# Schematic.net
KiCad netlist of a schematic drawn in Altium Designer
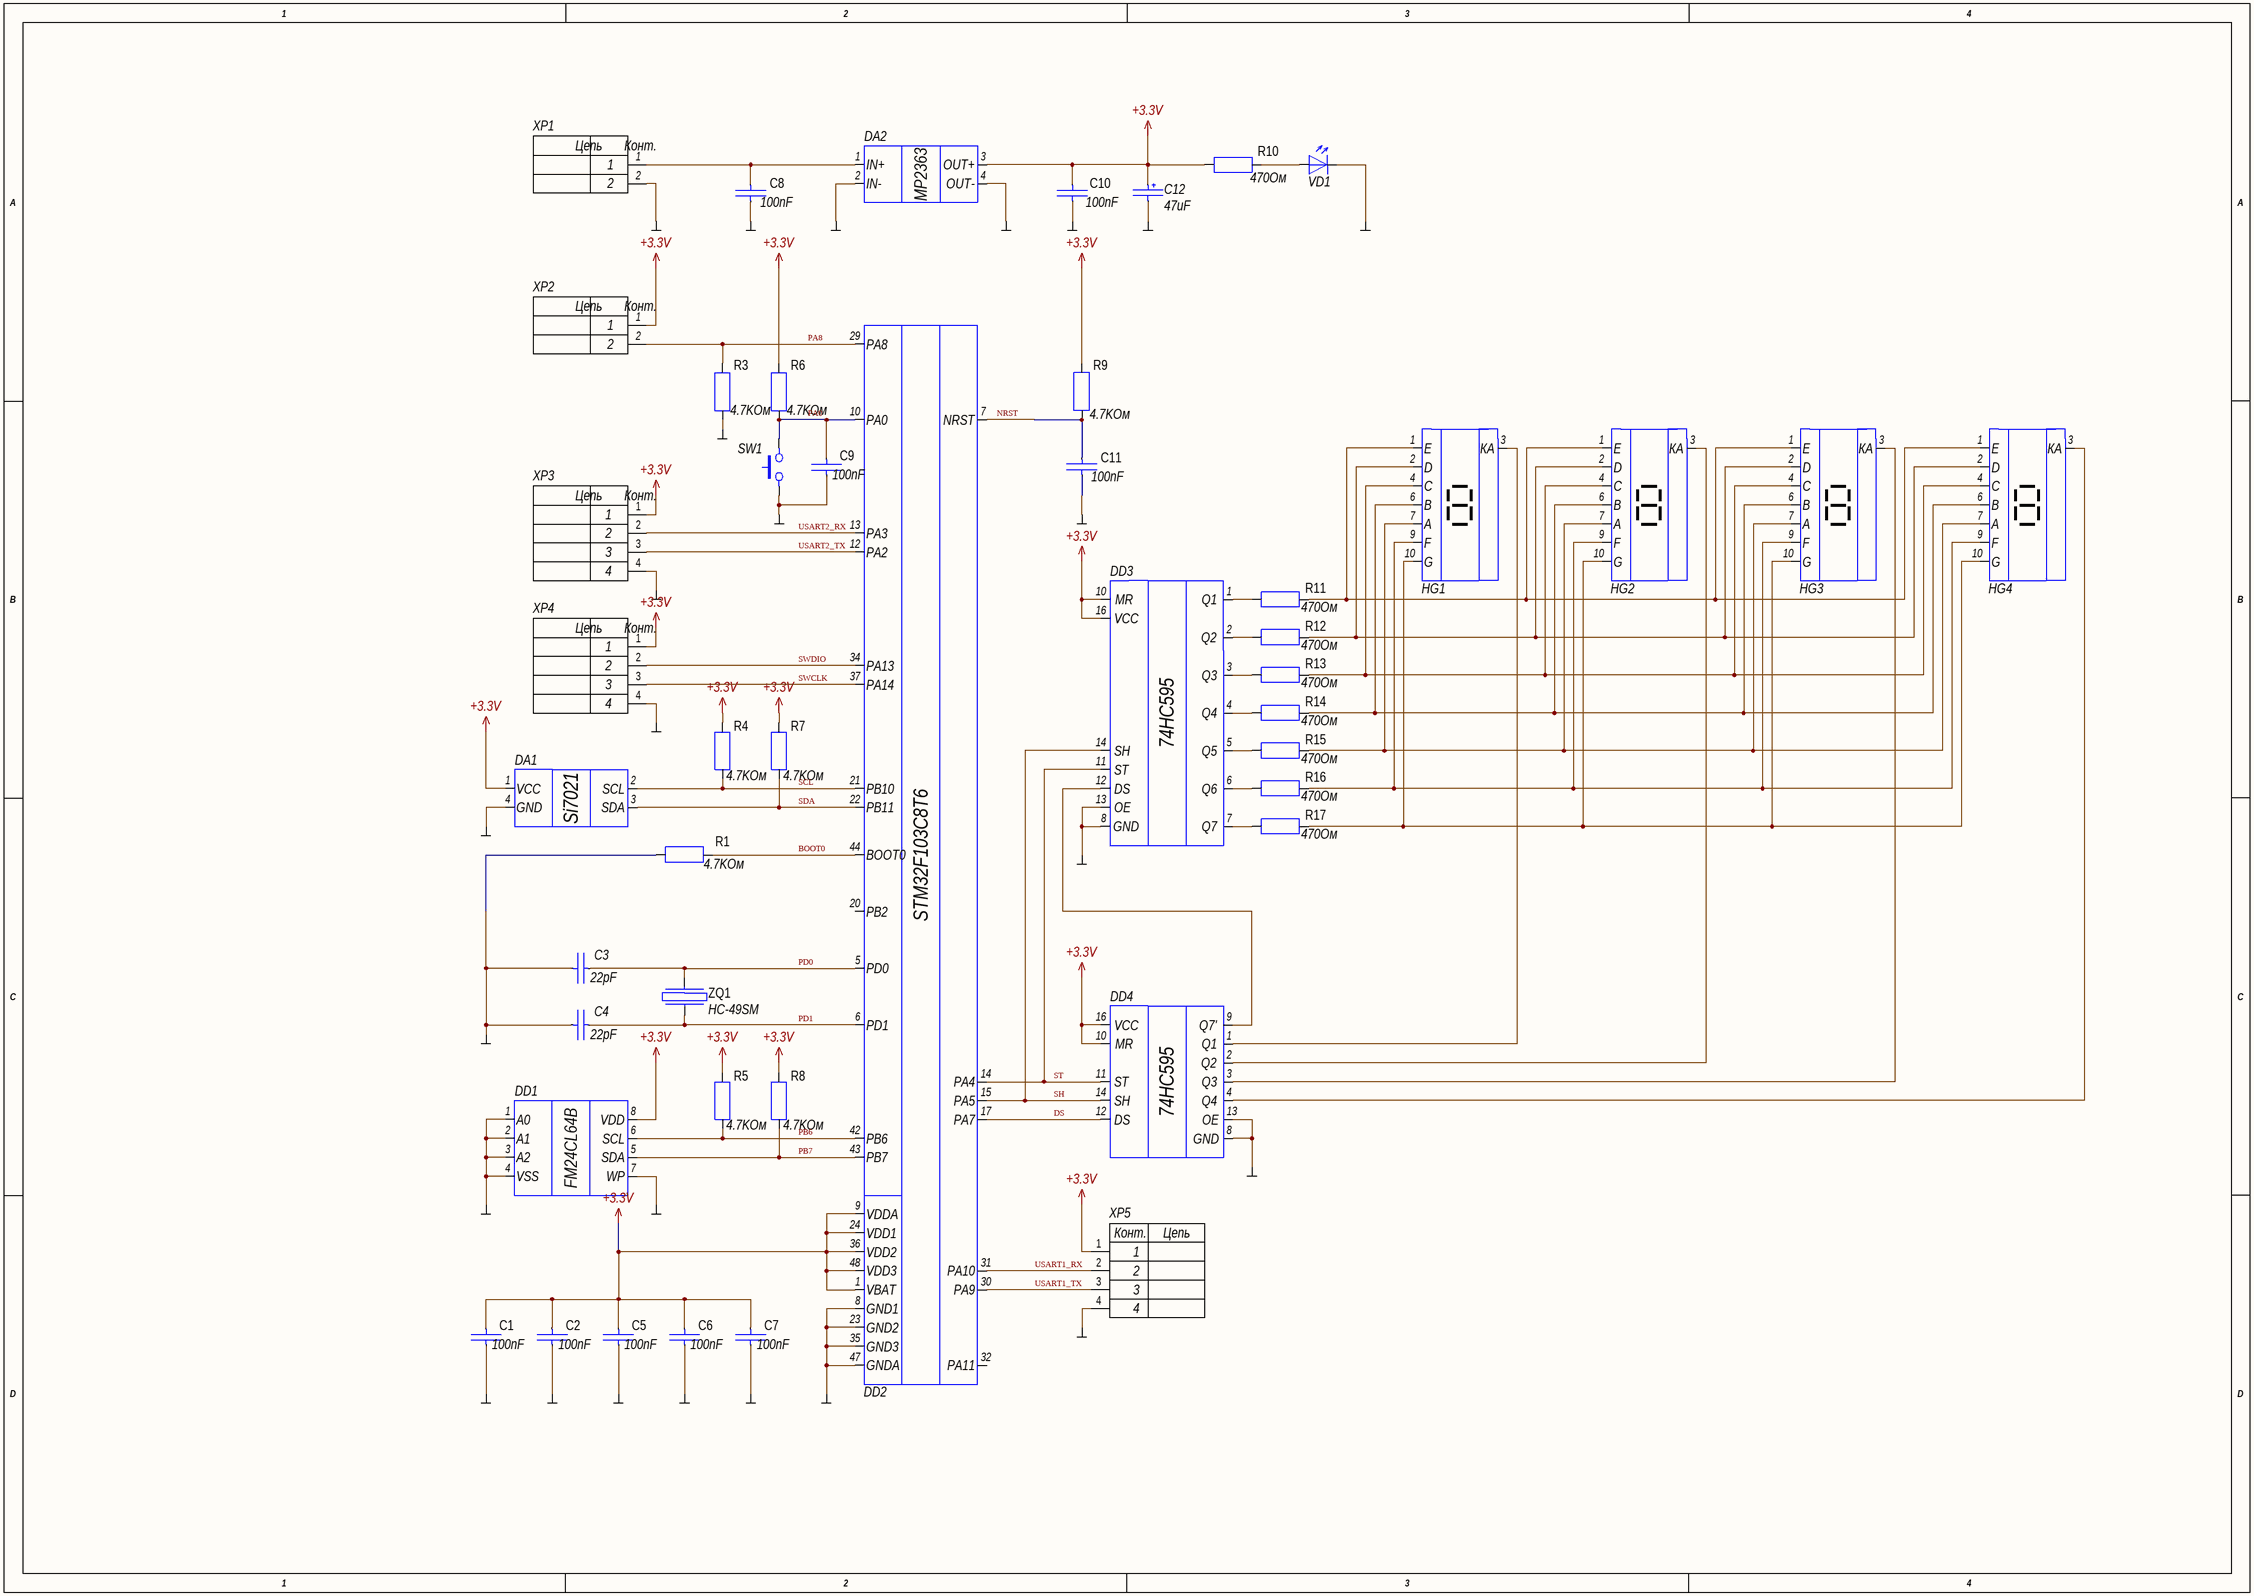
[diagram p0: Schematic.SchDoc]

(export (version "E")
  (design (tool "Eeschema 10.0.6"))
  (components
    (comp (ref "C1")
      (value "100nF")
      (footprint "0805")
      (libsource (lib "capisitor") (part "CAP{colon} 100nF"))
    )
    (comp (ref "C2")
      (value "100nF")
      (footprint "0805")
      (libsource (lib "capisitor") (part "CAP{colon} 100nF"))
    )
    (comp (ref "C3") (value "22pF") (footprint "0805") (libsource (lib "capisitor") (part "CAP{colon} 22pF")))
    (comp (ref "C4") (value "22pF") (footprint "0805") (libsource (lib "capisitor") (part "CAP{colon} 22pF")))
    (comp (ref "C5")
      (value "100nF")
      (footprint "0805")
      (libsource (lib "capisitor") (part "CAP{colon} 100nF"))
    )
    (comp (ref "C6")
      (value "100nF")
      (footprint "0805")
      (libsource (lib "capisitor") (part "CAP{colon} 100nF"))
    )
    (comp (ref "C7")
      (value "100nF")
      (footprint "0805")
      (libsource (lib "capisitor") (part "CAP{colon} 100nF"))
    )
    (comp (ref "C8")
      (value "100nF")
      (footprint "0805")
      (libsource (lib "capisitor") (part "CAP{colon} 100nF"))
    )
    (comp (ref "C9")
      (value "100nF")
      (footprint "0805")
      (libsource (lib "capisitor") (part "CAP{colon} 100nF"))
    )
    (comp (ref "C10")
      (value "100nF")
      (footprint "0805")
      (libsource (lib "capisitor") (part "CAP{colon} 100nF"))
    )
    (comp (ref "C11")
      (value "100nF")
      (footprint "0805")
      (libsource (lib "capisitor") (part "CAP{colon} 100nF"))
    )
    (comp (ref "C12")
      (value "47uF")
      (footprint "smdB")
      (libsource (lib "capisitor") (part "ECAP{colon} 47uF 10V"))
    )
    (comp (ref "DA1")
      (value "Si7021")
      (footprint "Si7021-Board")
      (libsource (lib "microcircuits") (part "Si7021"))
    )
    (comp (ref "DA2")
      (value "MP2363DN")
      (footprint "MP2363DN")
      (libsource (lib "microcircuits") (part "MP2363DN"))
    )
    (comp (ref "DD1")
      (value "FM24CL64B")
      (footprint "SOIC-8")
      (libsource (lib "microcircuits") (part "FM24CL64B"))
    )
    (comp (ref "DD2")
      (value "Component_1")
      (footprint "Quad48")
      (libsource (lib "stm32f103c8t6") (part "Component_1"))
    )
    (comp (ref "DD3")
      (value "74HC595_L")
      (footprint "74HC595")
      (libsource (lib "microcircuits") (part "74HC595_L"))
    )
    (comp (ref "DD4")
      (value "74HC595_S")
      (footprint "74HC595")
      (libsource (lib "microcircuits") (part "74HC595_S"))
    )
    (comp (ref "HG1")
      (value "7-Segment")
      (footprint "TOS-F2101AMRL-N-1-HF")
      (libsource (lib "LED") (part "7-Segment"))
    )
    (comp (ref "HG2")
      (value "7-Segment")
      (footprint "TOS-F2101AMRL-N-1-HF")
      (libsource (lib "LED") (part "7-Segment"))
    )
    (comp (ref "HG3")
      (value "7-Segment")
      (footprint "TOS-F2101AMRL-N-1-HF")
      (libsource (lib "LED") (part "7-Segment"))
    )
    (comp (ref "HG4")
      (value "7-Segment")
      (footprint "TOS-F2101AMRL-N-1-HF")
      (libsource (lib "LED") (part "7-Segment"))
    )
    (comp (ref "R1")
      (value "4.7KОм")
      (footprint "RES: 0.25w")
      (libsource (lib "resistors") (part "Resistor"))
    )
    (comp (ref "R3")
      (value "4.7KОм")
      (footprint "RES: 0.25w")
      (libsource (lib "resistors") (part "Resistor"))
    )
    (comp (ref "R4")
      (value "4.7KОм")
      (footprint "RES: 0.25w")
      (libsource (lib "resistors") (part "Resistor"))
    )
    (comp (ref "R5")
      (value "4.7KОм")
      (footprint "RES: 0.25w")
      (libsource (lib "resistors") (part "Resistor"))
    )
    (comp (ref "R6")
      (value "4.7KОм")
      (footprint "RES: 0.25w")
      (libsource (lib "resistors") (part "Resistor"))
    )
    (comp (ref "R7")
      (value "4.7KОм")
      (footprint "RES: 0.25w")
      (libsource (lib "resistors") (part "Resistor"))
    )
    (comp (ref "R8")
      (value "4.7KОм")
      (footprint "RES: 0.25w")
      (libsource (lib "resistors") (part "Resistor"))
    )
    (comp (ref "R9")
      (value "4.7KОм")
      (footprint "RES: 0.25w")
      (libsource (lib "resistors") (part "Resistor"))
    )
    (comp (ref "R10")
      (value "470Ом")
      (footprint "RES: 0.25w")
      (libsource (lib "resistors") (part "Resistor"))
    )
    (comp (ref "R11")
      (value "470Ом")
      (footprint "RES: 0.25w")
      (libsource (lib "resistors") (part "Resistor"))
    )
    (comp (ref "R12")
      (value "470Ом")
      (footprint "RES: 0.25w")
      (libsource (lib "resistors") (part "Resistor"))
    )
    (comp (ref "R13")
      (value "470Ом")
      (footprint "RES: 0.25w")
      (libsource (lib "resistors") (part "Resistor"))
    )
    (comp (ref "R14")
      (value "470Ом")
      (footprint "RES: 0.25w")
      (libsource (lib "resistors") (part "Resistor"))
    )
    (comp (ref "R15")
      (value "470Ом")
      (footprint "RES: 0.25w")
      (libsource (lib "resistors") (part "Resistor"))
    )
    (comp (ref "R16")
      (value "470Ом")
      (footprint "RES: 0.25w")
      (libsource (lib "resistors") (part "Resistor"))
    )
    (comp (ref "R17")
      (value "470Ом")
      (footprint "RES: 0.25w")
      (libsource (lib "resistors") (part "Resistor"))
    )
    (comp (ref "SW1") (value "Switch") (footprint "Button") (libsource (lib "switch") (part "Switch")))
    (comp (ref "VD1") (value "Diode") (footprint "TO-1608BC-BF") (libsource (lib "LED") (part "Diode")))
    (comp (ref "XP1") (value "X2") (footprint "DS-261A") (libsource (lib "xenya") (part "X2")))
    (comp (ref "XP2") (value "X2") (footprint "WB-02") (libsource (lib "xenya") (part "X2")))
    (comp (ref "XP3") (value "X4") (footprint "WB-04") (libsource (lib "xenya") (part "X4")))
    (comp (ref "XP4") (value "X4") (footprint "PLS-4") (libsource (lib "xenya") (part "X4")))
    (comp (ref "XP5") (value "X4") (footprint "WB-04") (libsource (lib "xenya") (part "X4")))
    (comp (ref "ZQ1") (value "HC-49SM") (footprint "HC-49SM") (libsource (lib "crystall") (part "HC-49SM")))
  )
  (nets
    (net (code "1") (name "+3.3V") (class "Default")
      (node (ref "C1") (pin "2") (pinfunction "2_2") (pintype "passive"))
      (node (ref "C10") (pin "2") (pinfunction "2_2") (pintype "passive"))
      (node (ref "C12") (pin "1") (pinfunction "1_1") (pintype "passive"))
      (node (ref "C2") (pin "2") (pinfunction "2_2") (pintype "passive"))
      (node (ref "C5") (pin "2") (pinfunction "2_2") (pintype "passive"))
      (node (ref "C6") (pin "2") (pinfunction "2_2") (pintype "passive"))
      (node (ref "C7") (pin "2") (pinfunction "2_2") (pintype "passive"))
      (node (ref "DA1") (pin "1") (pinfunction "VCC_1") (pintype "passive"))
      (node (ref "DA2") (pin "3") (pinfunction "OUT+_3") (pintype "passive"))
      (node (ref "DD1") (pin "8") (pinfunction "VDD_8") (pintype "passive"))
      (node (ref "DD2") (pin "1") (pinfunction "VBAT_1") (pintype "passive"))
      (node (ref "DD2") (pin "24") (pinfunction "VDD1_24") (pintype "passive"))
      (node (ref "DD2") (pin "36") (pinfunction "VDD2_36") (pintype "passive"))
      (node (ref "DD2") (pin "48") (pinfunction "VDD3_48") (pintype "passive"))
      (node (ref "DD2") (pin "9") (pinfunction "VDDA_9") (pintype "passive"))
      (node (ref "DD3") (pin "10") (pinfunction "MR_10") (pintype "passive"))
      (node (ref "DD3") (pin "16") (pinfunction "VCC_16") (pintype "passive"))
      (node (ref "DD4") (pin "10") (pinfunction "MR_10") (pintype "passive"))
      (node (ref "DD4") (pin "16") (pinfunction "VCC_16") (pintype "passive"))
      (node (ref "R10") (pin "1") (pinfunction "1_1") (pintype "passive"))
      (node (ref "R4") (pin "2") (pinfunction "2_2") (pintype "passive"))
      (node (ref "R5") (pin "2") (pinfunction "2_2") (pintype "passive"))
      (node (ref "R6") (pin "2") (pinfunction "2_2") (pintype "passive"))
      (node (ref "R7") (pin "2") (pinfunction "2_2") (pintype "passive"))
      (node (ref "R8") (pin "2") (pinfunction "2_2") (pintype "passive"))
      (node (ref "R9") (pin "2") (pinfunction "2_2") (pintype "passive"))
      (node (ref "XP2") (pin "1") (pintype "passive"))
      (node (ref "XP3") (pin "1") (pintype "passive"))
      (node (ref "XP4") (pin "1") (pintype "passive"))
      (node (ref "XP5") (pin "1") (pintype "passive"))
    )
    (net (code "2") (name "/BOOT0") (class "Default")
      (node (ref "DD2") (pin "44") (pinfunction "BOOT0_44") (pintype "passive"))
      (node (ref "R1") (pin "1") (pinfunction "1_1") (pintype "passive"))
    )
    (net (code "3") (name "/DS") (class "Default")
      (node (ref "DD2") (pin "17") (pinfunction "PA7_17") (pintype "passive"))
      (node (ref "DD4") (pin "12") (pinfunction "DS_12") (pintype "passive"))
    )
    (net (code "4") (name "/NRST") (class "Default")
      (node (ref "C11") (pin "2") (pinfunction "2_2") (pintype "passive"))
      (node (ref "DD2") (pin "7") (pinfunction "NRST_7") (pintype "passive"))
      (node (ref "R9") (pin "1") (pinfunction "1_1") (pintype "passive"))
    )
    (net (code "5") (name "/PA0") (class "Default")
      (node (ref "C9") (pin "2") (pinfunction "2_2") (pintype "passive"))
      (node (ref "DD2") (pin "10") (pinfunction "PA0_10") (pintype "passive"))
      (node (ref "R6") (pin "1") (pinfunction "1_1") (pintype "passive"))
      (node (ref "SW1") (pin "2") (pinfunction "2_2") (pintype "passive"))
    )
    (net (code "6") (name "/PA8") (class "Default")
      (node (ref "DD2") (pin "29") (pinfunction "PA8_29") (pintype "passive"))
      (node (ref "R3") (pin "2") (pinfunction "2_2") (pintype "passive"))
      (node (ref "XP2") (pin "2") (pintype "passive"))
    )
    (net (code "7") (name "/PB6") (class "Default")
      (node (ref "DD1") (pin "6") (pinfunction "SCL_6") (pintype "passive"))
      (node (ref "DD2") (pin "42") (pinfunction "PB6_42") (pintype "passive"))
      (node (ref "R5") (pin "1") (pinfunction "1_1") (pintype "passive"))
    )
    (net (code "8") (name "/PB7") (class "Default")
      (node (ref "DD1") (pin "5") (pinfunction "SDA_5") (pintype "passive"))
      (node (ref "DD2") (pin "43") (pinfunction "PB7_43") (pintype "passive"))
      (node (ref "R8") (pin "1") (pinfunction "1_1") (pintype "passive"))
    )
    (net (code "9") (name "/PD0") (class "Default")
      (node (ref "C3") (pin "2") (pinfunction "2_2") (pintype "passive"))
      (node (ref "DD2") (pin "5") (pinfunction "PD0_5") (pintype "passive"))
      (node (ref "ZQ1") (pin "1") (pintype "passive"))
    )
    (net (code "10") (name "/PD1") (class "Default")
      (node (ref "C4") (pin "2") (pinfunction "2_2") (pintype "passive"))
      (node (ref "DD2") (pin "6") (pinfunction "PD1_6") (pintype "passive"))
      (node (ref "ZQ1") (pin "2") (pintype "passive"))
    )
    (net (code "11") (name "/SCL") (class "Default")
      (node (ref "DA1") (pin "2") (pinfunction "SCL_2") (pintype "passive"))
      (node (ref "DD2") (pin "21") (pinfunction "PB10_21") (pintype "passive"))
      (node (ref "R4") (pin "1") (pinfunction "1_1") (pintype "passive"))
    )
    (net (code "12") (name "/SDA") (class "Default")
      (node (ref "DA1") (pin "3") (pinfunction "SDA_3") (pintype "passive"))
      (node (ref "DD2") (pin "22") (pinfunction "PB11_22") (pintype "passive"))
      (node (ref "R7") (pin "1") (pinfunction "1_1") (pintype "passive"))
    )
    (net (code "13") (name "/SH") (class "Default")
      (node (ref "DD2") (pin "15") (pinfunction "PA5_15") (pintype "passive"))
      (node (ref "DD3") (pin "14") (pinfunction "SH_14") (pintype "passive"))
      (node (ref "DD4") (pin "14") (pinfunction "SH_14") (pintype "passive"))
    )
    (net (code "14") (name "/ST") (class "Default")
      (node (ref "DD2") (pin "14") (pinfunction "PA4_14") (pintype "passive"))
      (node (ref "DD3") (pin "11") (pinfunction "ST_11") (pintype "passive"))
      (node (ref "DD4") (pin "11") (pinfunction "ST_11") (pintype "passive"))
    )
    (net (code "15") (name "/SWCLK") (class "Default")
      (node (ref "DD2") (pin "37") (pinfunction "PA14_37") (pintype "passive"))
      (node (ref "XP4") (pin "3") (pintype "passive"))
    )
    (net (code "16") (name "/SWDIO") (class "Default")
      (node (ref "DD2") (pin "34") (pinfunction "PA13_34") (pintype "passive"))
      (node (ref "XP4") (pin "2") (pintype "passive"))
    )
    (net (code "17") (name "/USART1_RX") (class "Default")
      (node (ref "DD2") (pin "31") (pinfunction "PA10_31") (pintype "passive"))
      (node (ref "XP5") (pin "2") (pintype "passive"))
    )
    (net (code "18") (name "/USART1_TX") (class "Default")
      (node (ref "DD2") (pin "30") (pinfunction "PA9_30") (pintype "passive"))
      (node (ref "XP5") (pin "3") (pintype "passive"))
    )
    (net (code "19") (name "/USART2_RX") (class "Default")
      (node (ref "DD2") (pin "13") (pinfunction "PA3_13") (pintype "passive"))
      (node (ref "XP3") (pin "2") (pintype "passive"))
    )
    (net (code "20") (name "/USART2_TX") (class "Default")
      (node (ref "DD2") (pin "12") (pinfunction "PA2_12") (pintype "passive"))
      (node (ref "XP3") (pin "3") (pintype "passive"))
    )
    (net (code "21") (name "GND") (class "Default")
      (node (ref "C1") (pin "1") (pinfunction "0_1") (pintype "passive"))
      (node (ref "C10") (pin "1") (pinfunction "0_1") (pintype "passive"))
      (node (ref "C11") (pin "1") (pinfunction "0_1") (pintype "passive"))
      (node (ref "C12") (pin "2") (pinfunction "2_2") (pintype "passive"))
      (node (ref "C2") (pin "1") (pinfunction "0_1") (pintype "passive"))
      (node (ref "C3") (pin "1") (pinfunction "0_1") (pintype "passive"))
      (node (ref "C4") (pin "1") (pinfunction "0_1") (pintype "passive"))
      (node (ref "C5") (pin "1") (pinfunction "0_1") (pintype "passive"))
      (node (ref "C6") (pin "1") (pinfunction "0_1") (pintype "passive"))
      (node (ref "C7") (pin "1") (pinfunction "0_1") (pintype "passive"))
      (node (ref "C8") (pin "1") (pinfunction "0_1") (pintype "passive"))
      (node (ref "C9") (pin "1") (pinfunction "0_1") (pintype "passive"))
      (node (ref "DA1") (pin "4") (pinfunction "GND_4") (pintype "passive"))
      (node (ref "DA2") (pin "2") (pinfunction "IN-_2") (pintype "passive"))
      (node (ref "DA2") (pin "4") (pinfunction "OUT-_4") (pintype "passive"))
      (node (ref "DD1") (pin "1") (pinfunction "A0_1") (pintype "passive"))
      (node (ref "DD1") (pin "2") (pinfunction "A1_2") (pintype "passive"))
      (node (ref "DD1") (pin "3") (pinfunction "A2_3") (pintype "passive"))
      (node (ref "DD1") (pin "4") (pinfunction "VSS_4") (pintype "passive"))
      (node (ref "DD1") (pin "7") (pinfunction "WP_7") (pintype "passive"))
      (node (ref "DD2") (pin "23") (pinfunction "GND2_23") (pintype "passive"))
      (node (ref "DD2") (pin "35") (pinfunction "GND3_35") (pintype "passive"))
      (node (ref "DD2") (pin "47") (pinfunction "GNDA_47") (pintype "passive"))
      (node (ref "DD2") (pin "8") (pinfunction "GND1_8") (pintype "passive"))
      (node (ref "DD3") (pin "13") (pinfunction "OE_13") (pintype "passive"))
      (node (ref "DD3") (pin "8") (pinfunction "GND_8") (pintype "passive"))
      (node (ref "DD4") (pin "13") (pinfunction "OE_13") (pintype "passive"))
      (node (ref "DD4") (pin "8") (pinfunction "GND_8") (pintype "passive"))
      (node (ref "R1") (pin "2") (pinfunction "2_2") (pintype "passive"))
      (node (ref "R3") (pin "1") (pinfunction "1_1") (pintype "passive"))
      (node (ref "SW1") (pin "1") (pinfunction "1_1") (pintype "passive"))
      (node (ref "VD1") (pin "2") (pinfunction "2_2") (pintype "passive"))
      (node (ref "XP1") (pin "2") (pintype "passive"))
      (node (ref "XP3") (pin "4") (pintype "passive"))
      (node (ref "XP4") (pin "4") (pintype "passive"))
      (node (ref "XP5") (pin "4") (pintype "passive"))
    )
    (net (code "22") (name "Net-(DA2-IN+)") (class "Default")
      (node (ref "C8") (pin "2") (pinfunction "2_2") (pintype "passive"))
      (node (ref "DA2") (pin "1") (pinfunction "IN+_1") (pintype "passive"))
      (node (ref "XP1") (pin "1") (pintype "passive"))
    )
    (net (code "23") (name "Net-(DD3-DS)") (class "Default")
      (node (ref "DD3") (pin "12") (pinfunction "DS_12") (pintype "passive"))
      (node (ref "DD4") (pin "9") (pinfunction "Q7'_9") (pintype "passive"))
    )
    (net (code "24") (name "Net-(DD3-Q1)") (class "Default")
      (node (ref "DD3") (pin "1") (pinfunction "Q1_1") (pintype "passive"))
      (node (ref "R11") (pin "2") (pinfunction "2_2") (pintype "passive"))
    )
    (net (code "25") (name "Net-(DD3-Q2)") (class "Default")
      (node (ref "DD3") (pin "2") (pinfunction "Q2_2") (pintype "passive"))
      (node (ref "R12") (pin "2") (pinfunction "2_2") (pintype "passive"))
    )
    (net (code "26") (name "Net-(DD3-Q3)") (class "Default")
      (node (ref "DD3") (pin "3") (pinfunction "Q3_3") (pintype "passive"))
      (node (ref "R13") (pin "2") (pinfunction "2_2") (pintype "passive"))
    )
    (net (code "27") (name "Net-(DD3-Q4)") (class "Default")
      (node (ref "DD3") (pin "4") (pinfunction "Q4_4") (pintype "passive"))
      (node (ref "R14") (pin "2") (pinfunction "2_2") (pintype "passive"))
    )
    (net (code "28") (name "Net-(DD3-Q5)") (class "Default")
      (node (ref "DD3") (pin "5") (pinfunction "Q5_5") (pintype "passive"))
      (node (ref "R15") (pin "2") (pinfunction "2_2") (pintype "passive"))
    )
    (net (code "29") (name "Net-(DD3-Q6)") (class "Default")
      (node (ref "DD3") (pin "6") (pinfunction "Q6_6") (pintype "passive"))
      (node (ref "R16") (pin "2") (pinfunction "2_2") (pintype "passive"))
    )
    (net (code "30") (name "Net-(DD3-Q7)") (class "Default")
      (node (ref "DD3") (pin "7") (pinfunction "Q7_7") (pintype "passive"))
      (node (ref "R17") (pin "2") (pinfunction "2_2") (pintype "passive"))
    )
    (net (code "31") (name "Net-(DD4-Q1)") (class "Default")
      (node (ref "DD4") (pin "1") (pinfunction "Q1_1") (pintype "passive"))
      (node (ref "HG1") (pin "3") (pinfunction "КА_3") (pintype "passive"))
    )
    (net (code "32") (name "Net-(DD4-Q2)") (class "Default")
      (node (ref "DD4") (pin "2") (pinfunction "Q2_2") (pintype "passive"))
      (node (ref "HG2") (pin "3") (pinfunction "КА_3") (pintype "passive"))
    )
    (net (code "33") (name "Net-(DD4-Q3)") (class "Default")
      (node (ref "DD4") (pin "3") (pinfunction "Q3_3") (pintype "passive"))
      (node (ref "HG3") (pin "3") (pinfunction "КА_3") (pintype "passive"))
    )
    (net (code "34") (name "Net-(DD4-Q4)") (class "Default")
      (node (ref "DD4") (pin "4") (pinfunction "Q4_4") (pintype "passive"))
      (node (ref "HG4") (pin "3") (pinfunction "КА_3") (pintype "passive"))
    )
    (net (code "35") (name "Net-(HG1-A)") (class "Default")
      (node (ref "HG1") (pin "7") (pinfunction "A_7") (pintype "passive"))
      (node (ref "HG2") (pin "7") (pinfunction "A_7") (pintype "passive"))
      (node (ref "HG3") (pin "7") (pinfunction "A_7") (pintype "passive"))
      (node (ref "HG4") (pin "7") (pinfunction "A_7") (pintype "passive"))
      (node (ref "R15") (pin "1") (pinfunction "1_1") (pintype "passive"))
    )
    (net (code "36") (name "Net-(HG1-B)") (class "Default")
      (node (ref "HG1") (pin "6") (pinfunction "B_6") (pintype "passive"))
      (node (ref "HG2") (pin "6") (pinfunction "B_6") (pintype "passive"))
      (node (ref "HG3") (pin "6") (pinfunction "B_6") (pintype "passive"))
      (node (ref "HG4") (pin "6") (pinfunction "B_6") (pintype "passive"))
      (node (ref "R14") (pin "1") (pinfunction "1_1") (pintype "passive"))
    )
    (net (code "37") (name "Net-(HG1-C)") (class "Default")
      (node (ref "HG1") (pin "4") (pinfunction "C_4") (pintype "passive"))
      (node (ref "HG2") (pin "4") (pinfunction "C_4") (pintype "passive"))
      (node (ref "HG3") (pin "4") (pinfunction "C_4") (pintype "passive"))
      (node (ref "HG4") (pin "4") (pinfunction "C_4") (pintype "passive"))
      (node (ref "R13") (pin "1") (pinfunction "1_1") (pintype "passive"))
    )
    (net (code "38") (name "Net-(HG1-D)") (class "Default")
      (node (ref "HG1") (pin "2") (pinfunction "D_2") (pintype "passive"))
      (node (ref "HG2") (pin "2") (pinfunction "D_2") (pintype "passive"))
      (node (ref "HG3") (pin "2") (pinfunction "D_2") (pintype "passive"))
      (node (ref "HG4") (pin "2") (pinfunction "D_2") (pintype "passive"))
      (node (ref "R12") (pin "1") (pinfunction "1_1") (pintype "passive"))
    )
    (net (code "39") (name "Net-(HG1-E)") (class "Default")
      (node (ref "HG1") (pin "1") (pinfunction "E_1") (pintype "passive"))
      (node (ref "HG2") (pin "1") (pinfunction "E_1") (pintype "passive"))
      (node (ref "HG3") (pin "1") (pinfunction "E_1") (pintype "passive"))
      (node (ref "HG4") (pin "1") (pinfunction "E_1") (pintype "passive"))
      (node (ref "R11") (pin "1") (pinfunction "1_1") (pintype "passive"))
    )
    (net (code "40") (name "Net-(HG1-F)") (class "Default")
      (node (ref "HG1") (pin "9") (pinfunction "F_9") (pintype "passive"))
      (node (ref "HG2") (pin "9") (pinfunction "F_9") (pintype "passive"))
      (node (ref "HG3") (pin "9") (pinfunction "F_9") (pintype "passive"))
      (node (ref "HG4") (pin "9") (pinfunction "F_9") (pintype "passive"))
      (node (ref "R16") (pin "1") (pinfunction "1_1") (pintype "passive"))
    )
    (net (code "41") (name "Net-(HG1-G)") (class "Default")
      (node (ref "HG1") (pin "10") (pinfunction "G_10") (pintype "passive"))
      (node (ref "HG2") (pin "10") (pinfunction "G_10") (pintype "passive"))
      (node (ref "HG3") (pin "10") (pinfunction "G_10") (pintype "passive"))
      (node (ref "HG4") (pin "10") (pinfunction "G_10") (pintype "passive"))
      (node (ref "R17") (pin "1") (pinfunction "1_1") (pintype "passive"))
    )
    (net (code "42") (name "Net-(R10-Pad2)") (class "Default")
      (node (ref "R10") (pin "2") (pinfunction "2_2") (pintype "passive"))
      (node (ref "VD1") (pin "1") (pinfunction "1_1") (pintype "passive"))
    )
    (net (code "43") (name "unconnected-(DD2-PA11-Pad32)") (class "Default")
      (node (ref "DD2") (pin "32") (pinfunction "PA11_32") (pintype "passive"))
    )
    (net (code "44") (name "unconnected-(DD2-PB2-Pad20)") (class "Default")
      (node (ref "DD2") (pin "20") (pinfunction "PB2_20") (pintype "passive"))
    )
  )
)
